# hev-controller_1_0.net
KiCad netlist of a schematic drawn in EAGLE
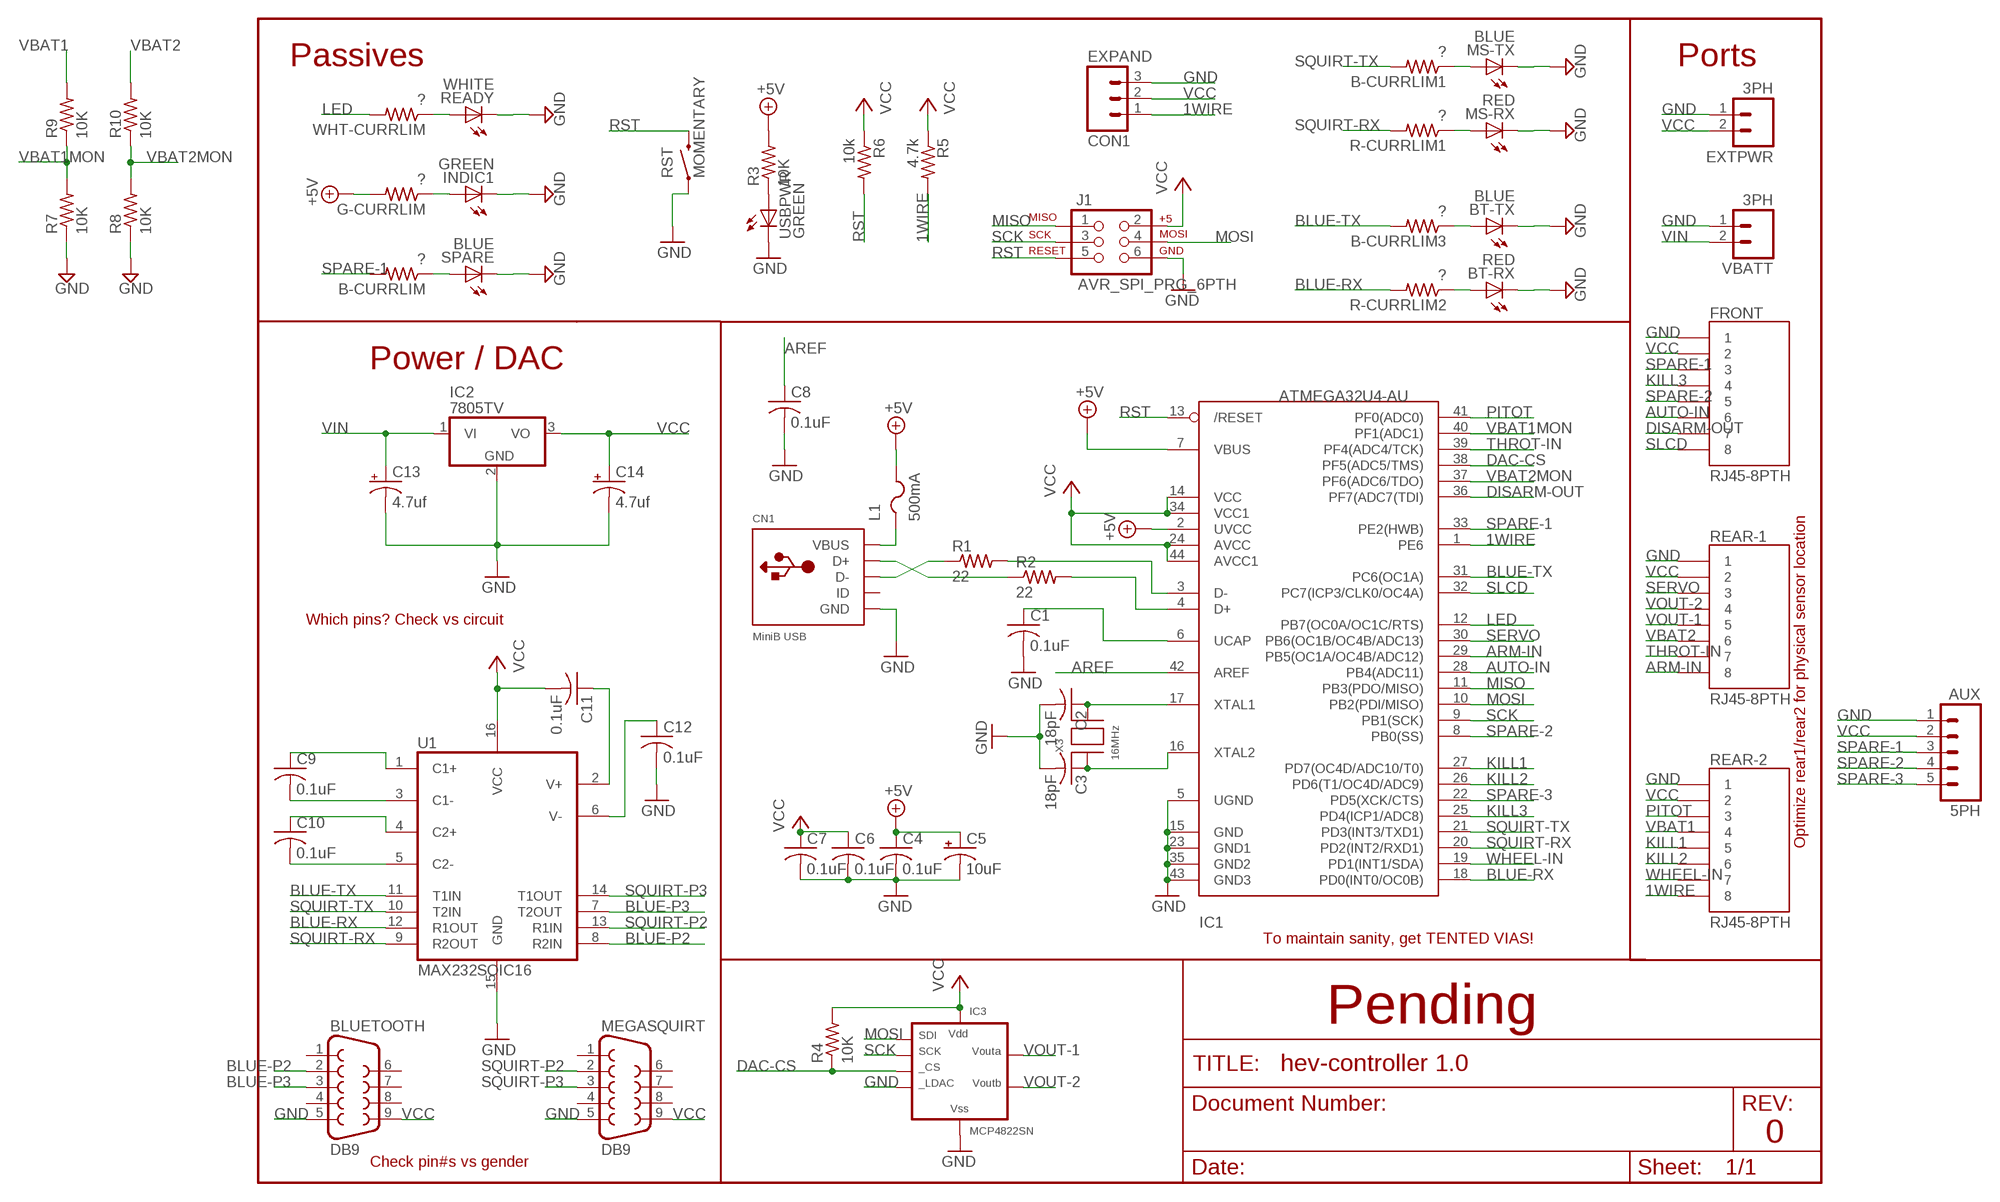
[diagram p0: schematic, sheet 1]

(export (version "E")
  (design (tool "Eeschema 10.0.6"))
  (components
    (comp (ref "5PH")
      (value "AUX")
      (footprint "eagle-import:1X05")
      (libsource (lib "eagle-import") (part "M05PTH"))
    )
    (comp (ref "B-CURRLIM")
      (value "?")
      (footprint "eagle-import:R0805")
      (libsource (lib "eagle-import") (part "R-US_R0805"))
    )
    (comp (ref "B-CURRLIM1")
      (value "?")
      (footprint "eagle-import:R0805")
      (libsource (lib "eagle-import") (part "R-US_R0805"))
    )
    (comp (ref "B-CURRLIM3")
      (value "?")
      (footprint "eagle-import:R0805")
      (libsource (lib "eagle-import") (part "R-US_R0805"))
    )
    (comp (ref "BLUETOOTH")
      (value "DB9")
      (footprint "eagle-import:DB9")
      (libsource (lib "eagle-import") (part "DB9"))
    )
    (comp (ref "BT-RX")
      (value "RED")
      (footprint "eagle-import:CHIPLED_0805")
      (libsource (lib "eagle-import") (part "LEDCHIPLED_0805"))
    )
    (comp (ref "BT-TX")
      (value "BLUE")
      (footprint "eagle-import:CHIPLED_0805")
      (libsource (lib "eagle-import") (part "LEDCHIPLED_0805"))
    )
    (comp (ref "C1")
      (value "0.1uF")
      (footprint "eagle-import:C0805K")
      (libsource (lib "eagle-import") (part "C-USC0805K"))
    )
    (comp (ref "C2")
      (value "18pF")
      (footprint "eagle-import:C0805K")
      (libsource (lib "eagle-import") (part "C-USC0805K"))
    )
    (comp (ref "C3")
      (value "18pF")
      (footprint "eagle-import:C0805K")
      (libsource (lib "eagle-import") (part "C-USC0805K"))
    )
    (comp (ref "C4")
      (value "0.1uF")
      (footprint "eagle-import:C0805K")
      (libsource (lib "eagle-import") (part "C-USC0805K"))
    )
    (comp (ref "C5")
      (value "10uF")
      (footprint "eagle-import:A_3216-18R")
      (libsource (lib "eagle-import") (part "CPOL-USA/3216-18R"))
    )
    (comp (ref "C6")
      (value "0.1uF")
      (footprint "eagle-import:C0805K")
      (libsource (lib "eagle-import") (part "C-USC0805K"))
    )
    (comp (ref "C7")
      (value "0.1uF")
      (footprint "eagle-import:C0805K")
      (libsource (lib "eagle-import") (part "C-USC0805K"))
    )
    (comp (ref "C8")
      (value "0.1uF")
      (footprint "eagle-import:C0805K")
      (libsource (lib "eagle-import") (part "C-USC0805K"))
    )
    (comp (ref "C9")
      (value "0.1uF")
      (footprint "eagle-import:C0805K")
      (libsource (lib "eagle-import") (part "C-USC0805K"))
    )
    (comp (ref "C10")
      (value "0.1uF")
      (footprint "eagle-import:C0805K")
      (libsource (lib "eagle-import") (part "C-USC0805K"))
    )
    (comp (ref "C11")
      (value "0.1uF")
      (footprint "eagle-import:C0805K")
      (libsource (lib "eagle-import") (part "C-USC0805K"))
    )
    (comp (ref "C12")
      (value "0.1uF")
      (footprint "eagle-import:C0805K")
      (libsource (lib "eagle-import") (part "C-USC0805K"))
    )
    (comp (ref "C13")
      (value "4.7uf")
      (footprint "eagle-import:E2,5-6")
      (libsource (lib "eagle-import") (part "rcl_CPOL-USE2.5-6"))
    )
    (comp (ref "C14")
      (value "4.7uf")
      (footprint "eagle-import:E2,5-6")
      (libsource (lib "eagle-import") (part "rcl_CPOL-USE2.5-6"))
    )
    (comp (ref "CN1")
      (value "MiniB USB")
      (footprint "eagle-import:USB-MINIB")
      (libsource (lib "eagle-import") (part "USBMINIB"))
    )
    (comp (ref "EXPAND")
      (value "CON1")
      (footprint "eagle-import:MOLEX-1X3")
      (libsource (lib "eagle-import") (part "M03POLAR"))
    )
    (comp (ref "EXTPWR")
      (value "3PH")
      (footprint "eagle-import:SCREWTERMINAL-3.5MM-2")
      (libsource (lib "eagle-import") (part "M023.5MM"))
    )
    (comp (ref "FRONT")
      (value "RJ45-8PTH")
      (footprint "eagle-import:RJ45-8")
      (libsource (lib "eagle-import") (part "RJ45-8PTH"))
    )
    (comp (ref "G-CURRLIM")
      (value "?")
      (footprint "eagle-import:R0805")
      (libsource (lib "eagle-import") (part "R-US_R0805"))
    )
    (comp (ref "IC1")
      (value "ATMEGA32U4-AU")
      (footprint "eagle-import:TQFP44")
      (libsource (lib "eagle-import") (part "ATMEGA32U4-AU"))
    )
    (comp (ref "IC2")
      (value "7805TV")
      (footprint "eagle-import:TO220V")
      (libsource (lib "eagle-import") (part "78TV05"))
    )
    (comp (ref "IC3")
      (value "MCP4822SN")
      (footprint "eagle-import:SO-08")
      (libsource (lib "eagle-import") (part "MCP4822SN"))
    )
    (comp (ref "INDIC1")
      (value "GREEN")
      (footprint "eagle-import:CHIPLED_0805")
      (libsource (lib "eagle-import") (part "LEDCHIPLED_0805"))
    )
    (comp (ref "J1")
      (value "AVR_SPI_PRG_6PTH")
      (footprint "eagle-import:2X3")
      (libsource (lib "eagle-import") (part "AVR_SPI_PRG_6PTH"))
    )
    (comp (ref "L1")
      (value "500mA")
      (footprint "eagle-import:R1206")
      (libsource (lib "eagle-import") (part "PTCFUSE-1206"))
    )
    (comp (ref "MEGASQUIRT")
      (value "DB9")
      (footprint "eagle-import:DB9")
      (libsource (lib "eagle-import") (part "DB9"))
    )
    (comp (ref "MS-RX")
      (value "RED")
      (footprint "eagle-import:CHIPLED_0805")
      (libsource (lib "eagle-import") (part "LEDCHIPLED_0805"))
    )
    (comp (ref "MS-TX")
      (value "BLUE")
      (footprint "eagle-import:CHIPLED_0805")
      (libsource (lib "eagle-import") (part "LEDCHIPLED_0805"))
    )
    (comp (ref "R-CURRLIM1")
      (value "?")
      (footprint "eagle-import:R0805")
      (libsource (lib "eagle-import") (part "R-US_R0805"))
    )
    (comp (ref "R-CURRLIM2")
      (value "?")
      (footprint "eagle-import:R0805")
      (libsource (lib "eagle-import") (part "R-US_R0805"))
    )
    (comp (ref "R1")
      (value "22")
      (footprint "eagle-import:R0805")
      (libsource (lib "eagle-import") (part "R-US_R0805"))
    )
    (comp (ref "R2")
      (value "22")
      (footprint "eagle-import:R0805")
      (libsource (lib "eagle-import") (part "R-US_R0805"))
    )
    (comp (ref "R3")
      (value "10K")
      (footprint "eagle-import:R0805")
      (libsource (lib "eagle-import") (part "R-US_R0805"))
    )
    (comp (ref "R4")
      (value "10K")
      (footprint "eagle-import:R0805")
      (libsource (lib "eagle-import") (part "R-US_R0805"))
    )
    (comp (ref "R5")
      (value "4.7k")
      (footprint "eagle-import:R0805")
      (libsource (lib "eagle-import") (part "R-US_R0805"))
    )
    (comp (ref "R6")
      (value "10k")
      (footprint "eagle-import:R0805")
      (libsource (lib "eagle-import") (part "R-US_R0805"))
    )
    (comp (ref "R7")
      (value "10K")
      (footprint "eagle-import:R0805")
      (libsource (lib "eagle-import") (part "R-US_R0805"))
    )
    (comp (ref "R8")
      (value "10K")
      (footprint "eagle-import:R0805")
      (libsource (lib "eagle-import") (part "R-US_R0805"))
    )
    (comp (ref "R9")
      (value "10K")
      (footprint "eagle-import:R0805")
      (libsource (lib "eagle-import") (part "R-US_R0805"))
    )
    (comp (ref "R10")
      (value "10K")
      (footprint "eagle-import:R0805")
      (libsource (lib "eagle-import") (part "R-US_R0805"))
    )
    (comp (ref "READY")
      (value "WHITE")
      (footprint "eagle-import:LED-1206")
      (libsource (lib "eagle-import") (part "LED1206"))
    )
    (comp (ref "REAR-1")
      (value "RJ45-8PTH")
      (footprint "eagle-import:RJ45-8")
      (libsource (lib "eagle-import") (part "RJ45-8PTH"))
    )
    (comp (ref "REAR-2")
      (value "RJ45-8PTH")
      (footprint "eagle-import:RJ45-8")
      (libsource (lib "eagle-import") (part "RJ45-8PTH"))
    )
    (comp (ref "RST")
      (value "MOMENTARY")
      (footprint "eagle-import:TACTILE-SWITCH-1101NE")
      (libsource (lib "eagle-import") (part "SWITCH-MOMENTARY-2-SMD-1101NE"))
    )
    (comp (ref "SPARE")
      (value "BLUE")
      (footprint "eagle-import:CHIPLED_0805")
      (libsource (lib "eagle-import") (part "LEDCHIPLED_0805"))
    )
    (comp (ref "U1")
      (value "MAX232SOIC16")
      (footprint "eagle-import:SO016")
      (libsource (lib "eagle-import") (part "MAX232SOIC16"))
    )
    (comp (ref "USBPWR")
      (value "GREEN")
      (footprint "eagle-import:CHIPLED_0805")
      (libsource (lib "eagle-import") (part "LEDCHIPLED_0805"))
    )
    (comp (ref "VBATT")
      (value "3PH")
      (footprint "eagle-import:SCREWTERMINAL-3.5MM-2")
      (libsource (lib "eagle-import") (part "M023.5MM"))
    )
    (comp (ref "WHT-CURRLIM")
      (value "?")
      (footprint "eagle-import:R0805")
      (libsource (lib "eagle-import") (part "R-US_R0805"))
    )
    (comp (ref "X3")
      (value "16MHz")
      (footprint "eagle-import:NX5032")
      (libsource (lib "eagle-import") (part "XTALNX5032"))
    )
  )
  (nets
    (net (code "1") (name "+5V") (class "Default")
      (node (ref "C4") (pin "1") (pinfunction "1_1") (pintype "passive"))
      (node (ref "C5") (pin "+") (pinfunction "+_+") (pintype "passive"))
      (node (ref "G-CURRLIM") (pin "2") (pinfunction "2_2") (pintype "passive"))
      (node (ref "IC1") (pin "2") (pinfunction "UVCC_2") (pintype "bidirectional"))
      (node (ref "IC1") (pin "7") (pinfunction "VBUS_7") (pintype "bidirectional"))
      (node (ref "L1") (pin "2") (pinfunction "2_2") (pintype "passive"))
      (node (ref "R3") (pin "2") (pinfunction "2_2") (pintype "passive"))
    )
    (net (code "2") (name "/1WIRE") (class "Default")
      (node (ref "EXPAND") (pin "1") (pinfunction "1_1") (pintype "passive"))
      (node (ref "IC1") (pin "1") (pinfunction "PE6_1") (pintype "bidirectional"))
      (node (ref "R5") (pin "2") (pinfunction "2_2") (pintype "passive"))
      (node (ref "REAR-2") (pin "8") (pinfunction "8_8") (pintype "bidirectional"))
    )
    (net (code "3") (name "/AREF") (class "Default")
      (node (ref "C8") (pin "1") (pinfunction "1_1") (pintype "passive"))
      (node (ref "IC1") (pin "42") (pinfunction "AREF_42") (pintype "bidirectional"))
    )
    (net (code "4") (name "/ARM-IN") (class "Default")
      (node (ref "IC1") (pin "29") (pinfunction "PB5(OC1A/OC4B/ADC12)_29") (pintype "bidirectional"))
      (node (ref "REAR-1") (pin "8") (pinfunction "8_8") (pintype "bidirectional"))
    )
    (net (code "5") (name "/AUTO-IN") (class "Default")
      (node (ref "FRONT") (pin "6") (pinfunction "6_6") (pintype "bidirectional"))
      (node (ref "IC1") (pin "28") (pinfunction "PB4(ADC11)_28") (pintype "bidirectional"))
    )
    (net (code "6") (name "/BLUE-P2") (class "Default")
      (node (ref "BLUETOOTH") (pin "2") (pinfunction "2_2") (pintype "passive"))
      (node (ref "U1") (pin "8") (pinfunction "R2IN_8") (pintype "input"))
    )
    (net (code "7") (name "/BLUE-P3") (class "Default")
      (node (ref "BLUETOOTH") (pin "3") (pinfunction "3_3") (pintype "passive"))
      (node (ref "U1") (pin "7") (pinfunction "T2OUT_7") (pintype "output"))
    )
    (net (code "8") (name "/BLUE-RX") (class "Default")
      (node (ref "IC1") (pin "18") (pinfunction "PD0(INT0/OC0B)_18") (pintype "bidirectional"))
      (node (ref "R-CURRLIM2") (pin "2") (pinfunction "2_2") (pintype "passive"))
      (node (ref "U1") (pin "12") (pinfunction "R1OUT_12") (pintype "output"))
    )
    (net (code "9") (name "/BLUE-TX") (class "Default")
      (node (ref "B-CURRLIM3") (pin "2") (pinfunction "2_2") (pintype "passive"))
      (node (ref "IC1") (pin "31") (pinfunction "PC6(OC1A)_31") (pintype "bidirectional"))
      (node (ref "U1") (pin "11") (pinfunction "T1IN_11") (pintype "input"))
    )
    (net (code "10") (name "/DAC-CS") (class "Default")
      (node (ref "IC1") (pin "38") (pinfunction "PF5(ADC5/TMS)_38") (pintype "bidirectional"))
      (node (ref "IC3") (pin "2") (pinfunction "CS_2") (pintype "input"))
      (node (ref "R4") (pin "1") (pinfunction "1_1") (pintype "passive"))
    )
    (net (code "11") (name "/DISARM-OUT") (class "Default")
      (node (ref "FRONT") (pin "7") (pinfunction "7_7") (pintype "bidirectional"))
      (node (ref "IC1") (pin "36") (pinfunction "PF7(ADC7(TDI)_36") (pintype "bidirectional"))
    )
    (net (code "12") (name "/KILL1") (class "Default")
      (node (ref "IC1") (pin "27") (pinfunction "PD7(OC4D/ADC10/T0)_27") (pintype "bidirectional"))
      (node (ref "REAR-2") (pin "5") (pinfunction "5_5") (pintype "bidirectional"))
    )
    (net (code "13") (name "/KILL2") (class "Default")
      (node (ref "IC1") (pin "26") (pinfunction "PD6(T1/OC4D/ADC9)_26") (pintype "bidirectional"))
      (node (ref "REAR-2") (pin "6") (pinfunction "6_6") (pintype "bidirectional"))
    )
    (net (code "14") (name "/KILL3") (class "Default")
      (node (ref "FRONT") (pin "4") (pinfunction "4_4") (pintype "bidirectional"))
      (node (ref "IC1") (pin "25") (pinfunction "PD4(ICP1/ADC8)_25") (pintype "bidirectional"))
    )
    (net (code "15") (name "/LED") (class "Default")
      (node (ref "IC1") (pin "12") (pinfunction "PB7(OC0A/OC1C/RTS)_12") (pintype "bidirectional"))
      (node (ref "WHT-CURRLIM") (pin "2") (pinfunction "2_2") (pintype "passive"))
    )
    (net (code "16") (name "/MISO") (class "Default")
      (node (ref "IC1") (pin "11") (pinfunction "PB3(PDO/MISO)_11") (pintype "bidirectional"))
      (node (ref "J1") (pin "1") (pinfunction "1_1") (pintype "passive"))
    )
    (net (code "17") (name "/MOSI") (class "Default")
      (node (ref "IC1") (pin "10") (pinfunction "PB2(PDI/MISO)_10") (pintype "bidirectional"))
      (node (ref "IC3") (pin "4") (pinfunction "SDI_4") (pintype "input"))
      (node (ref "J1") (pin "4") (pinfunction "4_4") (pintype "passive"))
    )
    (net (code "18") (name "/PITOT") (class "Default")
      (node (ref "IC1") (pin "41") (pinfunction "PF0(ADC0)_41") (pintype "bidirectional"))
      (node (ref "REAR-2") (pin "3") (pinfunction "3_3") (pintype "bidirectional"))
    )
    (net (code "19") (name "/RST") (class "Default")
      (node (ref "IC1") (pin "13") (pinfunction "/RESET_13") (pintype "bidirectional"))
      (node (ref "J1") (pin "5") (pinfunction "5_5") (pintype "passive"))
      (node (ref "R6") (pin "2") (pinfunction "2_2") (pintype "passive"))
      (node (ref "RST") (pin "P$2") (pinfunction "2_P$2") (pintype "passive"))
    )
    (net (code "20") (name "/SCK") (class "Default")
      (node (ref "IC1") (pin "9") (pinfunction "PB1(SCK)_9") (pintype "bidirectional"))
      (node (ref "IC3") (pin "3") (pinfunction "SCK_3") (pintype "input"))
      (node (ref "J1") (pin "3") (pinfunction "3_3") (pintype "passive"))
    )
    (net (code "21") (name "/SERVO") (class "Default")
      (node (ref "IC1") (pin "30") (pinfunction "PB6(OC1B/OC4B/ADC13)_30") (pintype "bidirectional"))
      (node (ref "REAR-1") (pin "3") (pinfunction "3_3") (pintype "bidirectional"))
    )
    (net (code "22") (name "/SLCD") (class "Default")
      (node (ref "FRONT") (pin "8") (pinfunction "8_8") (pintype "bidirectional"))
      (node (ref "IC1") (pin "32") (pinfunction "PC7(ICP3/CLK0/OC4A)_32") (pintype "bidirectional"))
    )
    (net (code "23") (name "/SPARE-1") (class "Default")
      (node (ref "5PH") (pin "3") (pinfunction "3_3") (pintype "passive"))
      (node (ref "B-CURRLIM") (pin "2") (pinfunction "2_2") (pintype "passive"))
      (node (ref "FRONT") (pin "3") (pinfunction "3_3") (pintype "bidirectional"))
      (node (ref "IC1") (pin "33") (pinfunction "PE2(HWB)_33") (pintype "bidirectional"))
    )
    (net (code "24") (name "/SPARE-2") (class "Default")
      (node (ref "5PH") (pin "4") (pinfunction "4_4") (pintype "passive"))
      (node (ref "FRONT") (pin "5") (pinfunction "5_5") (pintype "bidirectional"))
      (node (ref "IC1") (pin "8") (pinfunction "PB0(SS)_8") (pintype "bidirectional"))
    )
    (net (code "25") (name "/SPARE-3") (class "Default")
      (node (ref "5PH") (pin "5") (pinfunction "5_5") (pintype "passive"))
      (node (ref "IC1") (pin "22") (pinfunction "PD5(XCK/CTS)_22") (pintype "bidirectional"))
    )
    (net (code "26") (name "/SQUIRT-P2") (class "Default")
      (node (ref "MEGASQUIRT") (pin "2") (pinfunction "2_2") (pintype "passive"))
      (node (ref "U1") (pin "13") (pinfunction "R1IN_13") (pintype "input"))
    )
    (net (code "27") (name "/SQUIRT-P3") (class "Default")
      (node (ref "MEGASQUIRT") (pin "3") (pinfunction "3_3") (pintype "passive"))
      (node (ref "U1") (pin "14") (pinfunction "T1OUT_14") (pintype "output"))
    )
    (net (code "28") (name "/SQUIRT-RX") (class "Default")
      (node (ref "IC1") (pin "20") (pinfunction "PD2(INT2/RXD1)_20") (pintype "bidirectional"))
      (node (ref "R-CURRLIM1") (pin "2") (pinfunction "2_2") (pintype "passive"))
      (node (ref "U1") (pin "9") (pinfunction "R2OUT_9") (pintype "output"))
    )
    (net (code "29") (name "/SQUIRT-TX") (class "Default")
      (node (ref "B-CURRLIM1") (pin "2") (pinfunction "2_2") (pintype "passive"))
      (node (ref "IC1") (pin "21") (pinfunction "PD3(INT3/TXD1)_21") (pintype "bidirectional"))
      (node (ref "U1") (pin "10") (pinfunction "T2IN_10") (pintype "input"))
    )
    (net (code "30") (name "/THROT-IN") (class "Default")
      (node (ref "IC1") (pin "39") (pinfunction "PF4(ADC4/TCK)_39") (pintype "bidirectional"))
      (node (ref "REAR-1") (pin "7") (pinfunction "7_7") (pintype "bidirectional"))
    )
    (net (code "31") (name "/VBAT1") (class "Default")
      (node (ref "R9") (pin "2") (pinfunction "2_2") (pintype "passive"))
      (node (ref "REAR-2") (pin "4") (pinfunction "4_4") (pintype "bidirectional"))
    )
    (net (code "32") (name "/VBAT1MON") (class "Default")
      (node (ref "IC1") (pin "40") (pinfunction "PF1(ADC1)_40") (pintype "bidirectional"))
      (node (ref "R7") (pin "2") (pinfunction "2_2") (pintype "passive"))
      (node (ref "R9") (pin "1") (pinfunction "1_1") (pintype "passive"))
    )
    (net (code "33") (name "/VBAT2") (class "Default")
      (node (ref "R10") (pin "2") (pinfunction "2_2") (pintype "passive"))
      (node (ref "REAR-1") (pin "6") (pinfunction "6_6") (pintype "bidirectional"))
    )
    (net (code "34") (name "/VBAT2MON") (class "Default")
      (node (ref "IC1") (pin "37") (pinfunction "PF6(ADC6/TDO)_37") (pintype "bidirectional"))
      (node (ref "R10") (pin "1") (pinfunction "1_1") (pintype "passive"))
      (node (ref "R8") (pin "2") (pinfunction "2_2") (pintype "passive"))
    )
    (net (code "35") (name "/VIN") (class "Default")
      (node (ref "C13") (pin "+") (pinfunction "+_+") (pintype "passive"))
      (node (ref "IC2") (pin "1") (pinfunction "VI_1") (pintype "input"))
      (node (ref "VBATT") (pin "2") (pinfunction "2_2") (pintype "passive"))
    )
    (net (code "36") (name "/VOUT-1") (class "Default")
      (node (ref "IC3") (pin "8") (pinfunction "VOUTA_8") (pintype "output"))
      (node (ref "REAR-1") (pin "5") (pinfunction "5_5") (pintype "bidirectional"))
    )
    (net (code "37") (name "/VOUT-2") (class "Default")
      (node (ref "IC3") (pin "6") (pinfunction "VOUTB_6") (pintype "output"))
      (node (ref "REAR-1") (pin "4") (pinfunction "4_4") (pintype "bidirectional"))
    )
    (net (code "38") (name "/WHEEL-IN") (class "Default")
      (node (ref "IC1") (pin "19") (pinfunction "PD1(INT1/SDA)_19") (pintype "bidirectional"))
      (node (ref "REAR-2") (pin "7") (pinfunction "7_7") (pintype "bidirectional"))
    )
    (net (code "39") (name "GND") (class "Default")
      (node (ref "5PH") (pin "1") (pinfunction "1_1") (pintype "passive"))
      (node (ref "BLUETOOTH") (pin "5") (pinfunction "5_5") (pintype "passive"))
      (node (ref "BT-RX") (pin "C") (pinfunction "C_C") (pintype "passive"))
      (node (ref "BT-TX") (pin "C") (pinfunction "C_C") (pintype "passive"))
      (node (ref "C1") (pin "2") (pinfunction "2_2") (pintype "passive"))
      (node (ref "C12") (pin "2") (pinfunction "2_2") (pintype "passive"))
      (node (ref "C13") (pin "-") (pinfunction "-_-") (pintype "passive"))
      (node (ref "C14") (pin "-") (pinfunction "-_-") (pintype "passive"))
      (node (ref "C2") (pin "2") (pinfunction "2_2") (pintype "passive"))
      (node (ref "C3") (pin "2") (pinfunction "2_2") (pintype "passive"))
      (node (ref "C4") (pin "2") (pinfunction "2_2") (pintype "passive"))
      (node (ref "C5") (pin "-") (pinfunction "-_-") (pintype "passive"))
      (node (ref "C6") (pin "2") (pinfunction "2_2") (pintype "passive"))
      (node (ref "C7") (pin "2") (pinfunction "2_2") (pintype "passive"))
      (node (ref "C8") (pin "2") (pinfunction "2_2") (pintype "passive"))
      (node (ref "CN1") (pin "GND") (pinfunction "GND_GND") (pintype "power_in"))
      (node (ref "EXPAND") (pin "3") (pinfunction "3_3") (pintype "passive"))
      (node (ref "EXTPWR") (pin "1") (pinfunction "1_1") (pintype "passive"))
      (node (ref "FRONT") (pin "1") (pinfunction "1_1") (pintype "bidirectional"))
      (node (ref "IC1") (pin "15") (pinfunction "GND_15") (pintype "bidirectional"))
      (node (ref "IC1") (pin "23") (pinfunction "GND1_23") (pintype "bidirectional"))
      (node (ref "IC1") (pin "35") (pinfunction "GND2_35") (pintype "bidirectional"))
      (node (ref "IC1") (pin "43") (pinfunction "GND3_43") (pintype "bidirectional"))
      (node (ref "IC1") (pin "5") (pinfunction "UGND_5") (pintype "bidirectional"))
      (node (ref "IC2") (pin "2") (pinfunction "GND_2") (pintype "passive"))
      (node (ref "IC3") (pin "5") (pinfunction "LDAC_5") (pintype "input"))
      (node (ref "IC3") (pin "7") (pinfunction "VSS_7") (pintype "power_in"))
      (node (ref "INDIC1") (pin "C") (pinfunction "C_C") (pintype "passive"))
      (node (ref "J1") (pin "6") (pinfunction "6_6") (pintype "passive"))
      (node (ref "MEGASQUIRT") (pin "5") (pinfunction "5_5") (pintype "passive"))
      (node (ref "MS-RX") (pin "C") (pinfunction "C_C") (pintype "passive"))
      (node (ref "MS-TX") (pin "C") (pinfunction "C_C") (pintype "passive"))
      (node (ref "R7") (pin "1") (pinfunction "1_1") (pintype "passive"))
      (node (ref "R8") (pin "1") (pinfunction "1_1") (pintype "passive"))
      (node (ref "READY") (pin "C") (pinfunction "C_C") (pintype "passive"))
      (node (ref "REAR-1") (pin "1") (pinfunction "1_1") (pintype "bidirectional"))
      (node (ref "REAR-2") (pin "1") (pinfunction "1_1") (pintype "bidirectional"))
      (node (ref "RST") (pin "P$1") (pinfunction "1_P$1") (pintype "passive"))
      (node (ref "SPARE") (pin "C") (pinfunction "C_C") (pintype "passive"))
      (node (ref "U1") (pin "15") (pinfunction "GND_15") (pintype "bidirectional"))
      (node (ref "USBPWR") (pin "C") (pinfunction "C_C") (pintype "passive"))
      (node (ref "VBATT") (pin "1") (pinfunction "1_1") (pintype "passive"))
    )
    (net (code "40") (name "Net-(B-CURRLIM-Pad1)") (class "Default")
      (node (ref "B-CURRLIM") (pin "1") (pinfunction "1_1") (pintype "passive"))
      (node (ref "SPARE") (pin "A") (pinfunction "A_A") (pintype "passive"))
    )
    (net (code "41") (name "Net-(B-CURRLIM1-Pad1)") (class "Default")
      (node (ref "B-CURRLIM1") (pin "1") (pinfunction "1_1") (pintype "passive"))
      (node (ref "MS-TX") (pin "A") (pinfunction "A_A") (pintype "passive"))
    )
    (net (code "42") (name "Net-(B-CURRLIM3-Pad1)") (class "Default")
      (node (ref "B-CURRLIM3") (pin "1") (pinfunction "1_1") (pintype "passive"))
      (node (ref "BT-TX") (pin "A") (pinfunction "A_A") (pintype "passive"))
    )
    (net (code "43") (name "Net-(BT-RX-PadA)") (class "Default")
      (node (ref "BT-RX") (pin "A") (pinfunction "A_A") (pintype "passive"))
      (node (ref "R-CURRLIM2") (pin "1") (pinfunction "1_1") (pintype "passive"))
    )
    (net (code "44") (name "Net-(CN1-PadD+)") (class "Default")
      (node (ref "CN1") (pin "D+") (pinfunction "D+_D+") (pintype "bidirectional"))
      (node (ref "R2") (pin "1") (pinfunction "1_1") (pintype "passive"))
    )
    (net (code "45") (name "Net-(CN1-PadD-)") (class "Default")
      (node (ref "CN1") (pin "D-") (pinfunction "D-_D-") (pintype "bidirectional"))
      (node (ref "R1") (pin "1") (pinfunction "1_1") (pintype "passive"))
    )
    (net (code "46") (name "Net-(CN1-PadVBUS)") (class "Default")
      (node (ref "CN1") (pin "VBUS") (pinfunction "VBUS_VBUS") (pintype "power_in"))
      (node (ref "L1") (pin "1") (pinfunction "1_1") (pintype "passive"))
    )
    (net (code "47") (name "Net-(G-CURRLIM-Pad1)") (class "Default")
      (node (ref "G-CURRLIM") (pin "1") (pinfunction "1_1") (pintype "passive"))
      (node (ref "INDIC1") (pin "A") (pinfunction "A_A") (pintype "passive"))
    )
    (net (code "48") (name "Net-(IC1-D+)") (class "Default")
      (node (ref "IC1") (pin "4") (pinfunction "D+_4") (pintype "bidirectional"))
      (node (ref "R2") (pin "2") (pinfunction "2_2") (pintype "passive"))
    )
    (net (code "49") (name "Net-(IC1-D-)") (class "Default")
      (node (ref "IC1") (pin "3") (pinfunction "D-_3") (pintype "bidirectional"))
      (node (ref "R1") (pin "2") (pinfunction "2_2") (pintype "passive"))
    )
    (net (code "50") (name "Net-(IC1-UCAP)") (class "Default")
      (node (ref "C1") (pin "1") (pinfunction "1_1") (pintype "passive"))
      (node (ref "IC1") (pin "6") (pinfunction "UCAP_6") (pintype "bidirectional"))
    )
    (net (code "51") (name "Net-(IC1-XTAL1)") (class "Default")
      (node (ref "C2") (pin "1") (pinfunction "1_1") (pintype "passive"))
      (node (ref "IC1") (pin "17") (pinfunction "XTAL1_17") (pintype "bidirectional"))
      (node (ref "X3") (pin "P$2") (pinfunction "P$2_P$2") (pintype "bidirectional"))
    )
    (net (code "52") (name "Net-(IC1-XTAL2)") (class "Default")
      (node (ref "C3") (pin "1") (pinfunction "1_1") (pintype "passive"))
      (node (ref "IC1") (pin "16") (pinfunction "XTAL2_16") (pintype "bidirectional"))
      (node (ref "X3") (pin "P$1") (pinfunction "P$1_P$1") (pintype "bidirectional"))
    )
    (net (code "53") (name "Net-(MS-RX-PadA)") (class "Default")
      (node (ref "MS-RX") (pin "A") (pinfunction "A_A") (pintype "passive"))
      (node (ref "R-CURRLIM1") (pin "1") (pinfunction "1_1") (pintype "passive"))
    )
    (net (code "54") (name "Net-(R3-Pad1)") (class "Default")
      (node (ref "R3") (pin "1") (pinfunction "1_1") (pintype "passive"))
      (node (ref "USBPWR") (pin "A") (pinfunction "A_A") (pintype "passive"))
    )
    (net (code "55") (name "Net-(READY-PadA)") (class "Default")
      (node (ref "READY") (pin "A") (pinfunction "A_A") (pintype "passive"))
      (node (ref "WHT-CURRLIM") (pin "1") (pinfunction "1_1") (pintype "passive"))
    )
    (net (code "56") (name "Net-(U1-C1+)") (class "Default")
      (node (ref "C9") (pin "1") (pinfunction "1_1") (pintype "passive"))
      (node (ref "U1") (pin "1") (pinfunction "C1+_1") (pintype "bidirectional"))
    )
    (net (code "57") (name "Net-(U1-C1-)") (class "Default")
      (node (ref "C9") (pin "2") (pinfunction "2_2") (pintype "passive"))
      (node (ref "U1") (pin "3") (pinfunction "C1-_3") (pintype "bidirectional"))
    )
    (net (code "58") (name "Net-(U1-C2+)") (class "Default")
      (node (ref "C10") (pin "1") (pinfunction "1_1") (pintype "passive"))
      (node (ref "U1") (pin "4") (pinfunction "C2+_4") (pintype "bidirectional"))
    )
    (net (code "59") (name "Net-(U1-C2-)") (class "Default")
      (node (ref "C10") (pin "2") (pinfunction "2_2") (pintype "passive"))
      (node (ref "U1") (pin "5") (pinfunction "C2-_5") (pintype "bidirectional"))
    )
    (net (code "60") (name "Net-(U1-V+)") (class "Default")
      (node (ref "C11") (pin "1") (pinfunction "1_1") (pintype "passive"))
      (node (ref "U1") (pin "2") (pinfunction "V+_2") (pintype "bidirectional"))
    )
    (net (code "61") (name "Net-(U1-V-)") (class "Default")
      (node (ref "C12") (pin "1") (pinfunction "1_1") (pintype "passive"))
      (node (ref "U1") (pin "6") (pinfunction "V-_6") (pintype "bidirectional"))
    )
    (net (code "62") (name "VCC") (class "Default")
      (node (ref "5PH") (pin "2") (pinfunction "2_2") (pintype "passive"))
      (node (ref "BLUETOOTH") (pin "9") (pinfunction "9_9") (pintype "passive"))
      (node (ref "C11") (pin "2") (pinfunction "2_2") (pintype "passive"))
      (node (ref "C14") (pin "+") (pinfunction "+_+") (pintype "passive"))
      (node (ref "C6") (pin "1") (pinfunction "1_1") (pintype "passive"))
      (node (ref "C7") (pin "1") (pinfunction "1_1") (pintype "passive"))
      (node (ref "EXPAND") (pin "2") (pinfunction "2_2") (pintype "passive"))
      (node (ref "EXTPWR") (pin "2") (pinfunction "2_2") (pintype "passive"))
      (node (ref "FRONT") (pin "2") (pinfunction "2_2") (pintype "bidirectional"))
      (node (ref "IC1") (pin "14") (pinfunction "VCC_14") (pintype "bidirectional"))
      (node (ref "IC1") (pin "24") (pinfunction "AVCC_24") (pintype "bidirectional"))
      (node (ref "IC1") (pin "34") (pinfunction "VCC1_34") (pintype "bidirectional"))
      (node (ref "IC1") (pin "44") (pinfunction "AVCC1_44") (pintype "bidirectional"))
      (node (ref "IC2") (pin "3") (pinfunction "VO_3") (pintype "passive"))
      (node (ref "IC3") (pin "1") (pinfunction "VDD_1") (pintype "power_in"))
      (node (ref "J1") (pin "2") (pinfunction "2_2") (pintype "passive"))
      (node (ref "MEGASQUIRT") (pin "9") (pinfunction "9_9") (pintype "passive"))
      (node (ref "R4") (pin "2") (pinfunction "2_2") (pintype "passive"))
      (node (ref "R5") (pin "1") (pinfunction "1_1") (pintype "passive"))
      (node (ref "R6") (pin "1") (pinfunction "1_1") (pintype "passive"))
      (node (ref "REAR-1") (pin "2") (pinfunction "2_2") (pintype "bidirectional"))
      (node (ref "REAR-2") (pin "2") (pinfunction "2_2") (pintype "bidirectional"))
      (node (ref "U1") (pin "16") (pinfunction "VCC_16") (pintype "bidirectional"))
    )
    (net (code "63") (name "unconnected-(BLUETOOTH-Pad1)") (class "Default")
      (node (ref "BLUETOOTH") (pin "1") (pinfunction "1_1") (pintype "passive"))
    )
    (net (code "64") (name "unconnected-(BLUETOOTH-Pad4)") (class "Default")
      (node (ref "BLUETOOTH") (pin "4") (pinfunction "4_4") (pintype "passive"))
    )
    (net (code "65") (name "unconnected-(BLUETOOTH-Pad6)") (class "Default")
      (node (ref "BLUETOOTH") (pin "6") (pinfunction "6_6") (pintype "passive"))
    )
    (net (code "66") (name "unconnected-(BLUETOOTH-Pad7)") (class "Default")
      (node (ref "BLUETOOTH") (pin "7") (pinfunction "7_7") (pintype "passive"))
    )
    (net (code "67") (name "unconnected-(BLUETOOTH-Pad8)") (class "Default")
      (node (ref "BLUETOOTH") (pin "8") (pinfunction "8_8") (pintype "passive"))
    )
    (net (code "68") (name "unconnected-(CN1-PadID)") (class "Default")
      (node (ref "CN1") (pin "ID") (pinfunction "ID_ID") (pintype "bidirectional"))
    )
    (net (code "69") (name "unconnected-(MEGASQUIRT-Pad1)") (class "Default")
      (node (ref "MEGASQUIRT") (pin "1") (pinfunction "1_1") (pintype "passive"))
    )
    (net (code "70") (name "unconnected-(MEGASQUIRT-Pad4)") (class "Default")
      (node (ref "MEGASQUIRT") (pin "4") (pinfunction "4_4") (pintype "passive"))
    )
    (net (code "71") (name "unconnected-(MEGASQUIRT-Pad6)") (class "Default")
      (node (ref "MEGASQUIRT") (pin "6") (pinfunction "6_6") (pintype "passive"))
    )
    (net (code "72") (name "unconnected-(MEGASQUIRT-Pad7)") (class "Default")
      (node (ref "MEGASQUIRT") (pin "7") (pinfunction "7_7") (pintype "passive"))
    )
    (net (code "73") (name "unconnected-(MEGASQUIRT-Pad8)") (class "Default")
      (node (ref "MEGASQUIRT") (pin "8") (pinfunction "8_8") (pintype "passive"))
    )
  )
)
